# 2_0.net
KiCad netlist of a schematic drawn in Altium Designer
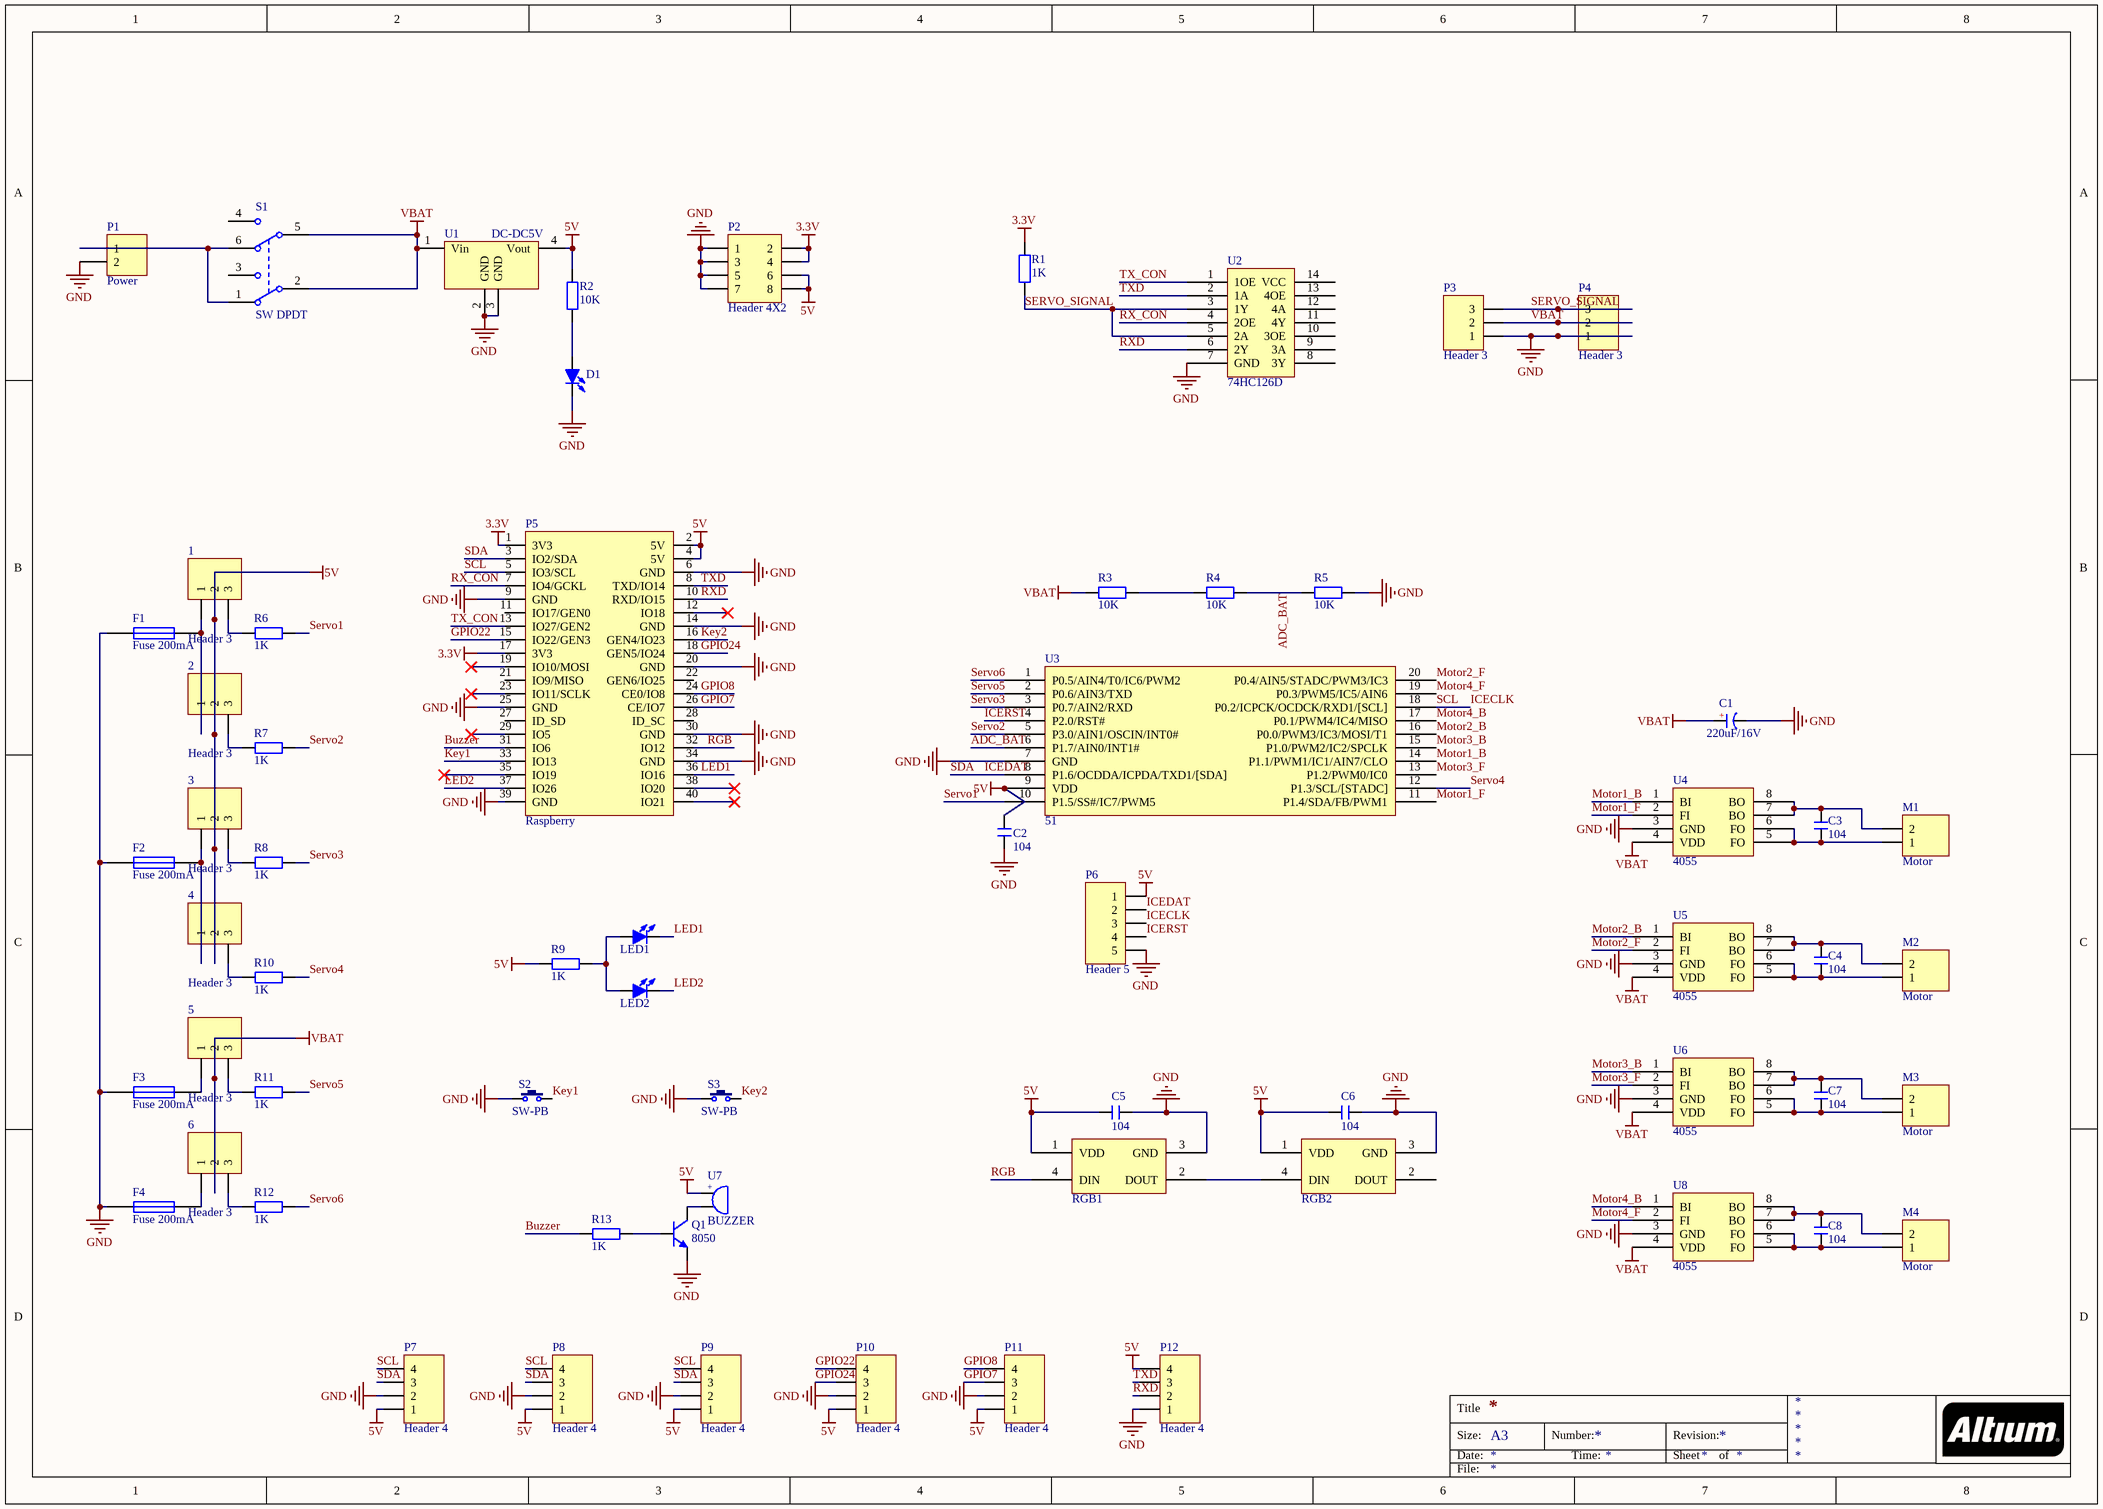
[diagram p0: 机械臂扩展板2.0.SchDoc]

(export (version "E")
  (design (tool "Eeschema 10.0.6"))
  (components
    (comp (ref "1")
      (value "Header 3")
      (footprint "HDR2.54-LI-3P")
      (description "舵机接口")
      (fields (field (name "版权归属") "源创客"))
      (libsource (lib "机械臂扩展板2.0") (part "Header 3"))
    )
    (comp (ref "2")
      (value "Header 3")
      (footprint "HDR2.54-LI-3P")
      (description "舵机接口")
      (fields (field (name "版权归属") "源创客"))
      (libsource (lib "机械臂扩展板2.0") (part "Header 3"))
    )
    (comp (ref "3")
      (value "Header 3")
      (footprint "HDR2.54-LI-3P")
      (description "舵机接口")
      (fields (field (name "版权归属") "源创客"))
      (libsource (lib "机械臂扩展板2.0") (part "Header 3"))
    )
    (comp (ref "4")
      (value "Header 3")
      (footprint "HDR2.54-LI-3P")
      (description "舵机接口")
      (fields (field (name "版权归属") "源创客"))
      (libsource (lib "机械臂扩展板2.0") (part "Header 3"))
    )
    (comp (ref "5")
      (value "Header 3")
      (footprint "HDR2.54-LI-3P")
      (description "舵机接口")
      (fields (field (name "版权归属") "源创客"))
      (libsource (lib "机械臂扩展板2.0") (part "Header 3"))
    )
    (comp (ref "6")
      (value "Header 3")
      (footprint "HDR2.54-LI-3P")
      (description "舵机接口")
      (fields (field (name "版权归属") "源创客"))
      (libsource (lib "机械臂扩展板2.0") (part "Header 3"))
    )
    (comp (ref "C1")
      (value "220uF/16V")
      (footprint "CM D(6.3*7.7)")
      (description "贴片电解电容")
      (fields (field (name "版权归属") "源创客"))
      (libsource (lib "机械臂扩展板2.0") (part "C-CM"))
    )
    (comp (ref "C2")
      (value "104")
      (footprint "C 0603_L")
      (description "无极性贴片电容")
      (fields (field (name "版权归属") "源创客"))
      (libsource (lib "机械臂扩展板2.0") (part "C"))
    )
    (comp (ref "C3")
      (value "104")
      (footprint "C 0603_L")
      (description "无极性贴片电容")
      (fields (field (name "版权归属") "源创客"))
      (libsource (lib "机械臂扩展板2.0") (part "C"))
    )
    (comp (ref "C4")
      (value "104")
      (footprint "C 0603_L")
      (description "无极性贴片电容")
      (fields (field (name "版权归属") "源创客"))
      (libsource (lib "机械臂扩展板2.0") (part "C"))
    )
    (comp (ref "C5")
      (value "104")
      (footprint "C 0603_L")
      (description "无极性贴片电容")
      (fields (field (name "版权归属") "源创客"))
      (libsource (lib "机械臂扩展板2.0") (part "C"))
    )
    (comp (ref "C6")
      (value "104")
      (footprint "C 0603_L")
      (description "无极性贴片电容")
      (fields (field (name "版权归属") "源创客"))
      (libsource (lib "机械臂扩展板2.0") (part "C"))
    )
    (comp (ref "C7")
      (value "104")
      (footprint "C 0603_L")
      (description "无极性贴片电容")
      (fields (field (name "版权归属") "源创客"))
      (libsource (lib "机械臂扩展板2.0") (part "C"))
    )
    (comp (ref "C8")
      (value "104")
      (footprint "C 0603_L")
      (description "无极性贴片电容")
      (fields (field (name "版权归属") "源创客"))
      (libsource (lib "机械臂扩展板2.0") (part "C"))
    )
    (comp (ref "D1")
      (value "红色")
      (footprint "LED 0603R")
      (description "贴片LED")
      (fields (field (name "版权归属") "源创客"))
      (libsource (lib "机械臂扩展板2.0") (part "LED-SMD"))
    )
    (comp (ref "F1")
      (value "Fuse 200mA")
      (footprint "F1206")
      (description "Fuse")
      (fields (field (name "PUBLISHER") "Altium Limited"))
      (libsource (lib "机械臂扩展板2.0") (part "Fuse 1"))
    )
    (comp (ref "F2")
      (value "Fuse 200mA")
      (footprint "F1206")
      (description "Fuse")
      (fields (field (name "PUBLISHER") "Altium Limited"))
      (libsource (lib "机械臂扩展板2.0") (part "Fuse 1"))
    )
    (comp (ref "F3")
      (value "Fuse 200mA")
      (footprint "F1206")
      (description "Fuse")
      (fields (field (name "PUBLISHER") "Altium Limited"))
      (libsource (lib "机械臂扩展板2.0") (part "Fuse 1"))
    )
    (comp (ref "F4")
      (value "Fuse 200mA")
      (footprint "F1206")
      (description "Fuse")
      (fields (field (name "PUBLISHER") "Altium Limited"))
      (libsource (lib "机械臂扩展板2.0") (part "Fuse 1"))
    )
    (comp (ref "LED1")
      (value "红色")
      (footprint "LED 0603G")
      (description "贴片LED")
      (fields (field (name "版权归属") "源创客"))
      (libsource (lib "机械臂扩展板2.0") (part "LED-SMD"))
    )
    (comp (ref "LED2")
      (value "红色")
      (footprint "LED 0603G")
      (description "贴片LED")
      (fields (field (name "版权归属") "源创客"))
      (libsource (lib "机械臂扩展板2.0") (part "LED-SMD"))
    )
    (comp (ref "M1")
      (value "Motor")
      (footprint "XH2.54-LI-2P")
      (description "2P接插件")
      (fields (field (name "版权归属") "源创客"))
      (libsource (lib "机械臂扩展板2.0") (part "Header 2"))
    )
    (comp (ref "M2")
      (value "Motor")
      (footprint "XH2.54-LI-2P")
      (description "2P接插件")
      (fields (field (name "版权归属") "源创客"))
      (libsource (lib "机械臂扩展板2.0") (part "Header 2"))
    )
    (comp (ref "M3")
      (value "Motor")
      (footprint "XH2.54-LI-2P")
      (description "2P接插件")
      (fields (field (name "版权归属") "源创客"))
      (libsource (lib "机械臂扩展板2.0") (part "Header 2"))
    )
    (comp (ref "M4")
      (value "Motor")
      (footprint "XH2.54-LI-2P")
      (description "2P接插件")
      (fields (field (name "版权归属") "源创客"))
      (libsource (lib "机械臂扩展板2.0") (part "Header 2"))
    )
    (comp (ref "P1") (value "Power") (footprint "KF128-3.81-2P") (libsource (lib "机械臂扩展板2.0") (part "Power")))
    (comp (ref "P2")
      (value "Header 4X2")
      (footprint "HDR2.54-LI-2x4P")
      (description "4*2P接插件")
      (fields (field (name "版权归属") "源创客"))
      (libsource (lib "机械臂扩展板2.0") (part "Header 4X2"))
    )
    (comp (ref "P3")
      (value "Header 3")
      (footprint "XH2.54-LI-3P")
      (description "舵机接口")
      (fields (field (name "版权归属") "源创客"))
      (libsource (lib "") (part "Header 3_2"))
    )
    (comp (ref "P4")
      (value "Header 3")
      (footprint "XH2.54-LI-3P")
      (description "舵机接口")
      (fields (field (name "版权归属") "源创客"))
      (libsource (lib "") (part "Header 3_1"))
    )
    (comp (ref "P6")
      (value "Header 5")
      (footprint "HDR2.54-LI-5P")
      (description "5P接插件")
      (fields (field (name "版权归属") "源创客"))
      (libsource (lib "机械臂扩展板2.0") (part "Header 5"))
    )
    (comp (ref "P7")
      (value "Header 4")
      (footprint "XH2.54-WI-4P")
      (description "I2C总线接口")
      (fields (field (name "版权归属") "源创客"))
      (libsource (lib "机械臂扩展板2.0") (part "Header 4"))
    )
    (comp (ref "P8")
      (value "Header 4")
      (footprint "XH2.54-WI-4P")
      (description "I2C总线接口")
      (fields (field (name "版权归属") "源创客"))
      (libsource (lib "机械臂扩展板2.0") (part "Header 4"))
    )
    (comp (ref "P9")
      (value "Header 4")
      (footprint "XH2.54-WI-4P")
      (description "I2C总线接口")
      (fields (field (name "版权归属") "源创客"))
      (libsource (lib "机械臂扩展板2.0") (part "Header 4"))
    )
    (comp (ref "P10")
      (value "Header 4")
      (footprint "XH2.54-LI-4P")
      (description "I2C总线接口")
      (fields (field (name "版权归属") "源创客"))
      (libsource (lib "机械臂扩展板2.0") (part "Header 4"))
    )
    (comp (ref "P11")
      (value "Header 4")
      (footprint "XH2.54-LI-4P")
      (description "I2C总线接口")
      (fields (field (name "版权归属") "源创客"))
      (libsource (lib "机械臂扩展板2.0") (part "Header 4"))
    )
    (comp (ref "P12")
      (value "Header 4")
      (footprint "HDR2.54-LI-4P")
      (description "I2C总线接口")
      (fields (field (name "版权归属") "源创客"))
      (libsource (lib "机械臂扩展板2.0") (part "Header 4"))
    )
    (comp (ref "Q1")
      (value "8050")
      (footprint "SOT23-3L")
      (description "高频放大-NPN型")
      (fields (field (name "版权归属") "源创客"))
      (libsource (lib "机械臂扩展板2.0") (part "8050-SMD"))
    )
    (comp (ref "R1")
      (value "1K")
      (footprint "R 0603_L")
      (description "贴片电阻")
      (fields (field (name "版权归属") "源创客"))
      (libsource (lib "机械臂扩展板2.0") (part "R"))
    )
    (comp (ref "R2")
      (value "10K")
      (footprint "R 0603_L")
      (description "贴片电阻")
      (fields (field (name "版权归属") "源创客"))
      (libsource (lib "机械臂扩展板2.0") (part "R"))
    )
    (comp (ref "R3")
      (value "10K")
      (footprint "R 0603_L")
      (description "贴片电阻")
      (fields (field (name "版权归属") "源创客"))
      (libsource (lib "机械臂扩展板2.0") (part "R"))
    )
    (comp (ref "R4")
      (value "10K")
      (footprint "R 0603_L")
      (description "贴片电阻")
      (fields (field (name "版权归属") "源创客"))
      (libsource (lib "机械臂扩展板2.0") (part "R"))
    )
    (comp (ref "R5")
      (value "10K")
      (footprint "R 0603_L")
      (description "贴片电阻")
      (fields (field (name "版权归属") "源创客"))
      (libsource (lib "机械臂扩展板2.0") (part "R"))
    )
    (comp (ref "R6")
      (value "1K")
      (footprint "R 0603_L")
      (description "贴片电阻")
      (fields (field (name "版权归属") "源创客"))
      (libsource (lib "机械臂扩展板2.0") (part "R"))
    )
    (comp (ref "R7")
      (value "1K")
      (footprint "R 0603_L")
      (description "贴片电阻")
      (fields (field (name "版权归属") "源创客"))
      (libsource (lib "机械臂扩展板2.0") (part "R"))
    )
    (comp (ref "R8")
      (value "1K")
      (footprint "R 0603_L")
      (description "贴片电阻")
      (fields (field (name "版权归属") "源创客"))
      (libsource (lib "机械臂扩展板2.0") (part "R"))
    )
    (comp (ref "R9")
      (value "1K")
      (footprint "R 0603_L")
      (description "贴片电阻")
      (fields (field (name "版权归属") "源创客"))
      (libsource (lib "机械臂扩展板2.0") (part "R"))
    )
    (comp (ref "R10")
      (value "1K")
      (footprint "R 0603_L")
      (description "贴片电阻")
      (fields (field (name "版权归属") "源创客"))
      (libsource (lib "机械臂扩展板2.0") (part "R"))
    )
    (comp (ref "R11")
      (value "1K")
      (footprint "R 0603_L")
      (description "贴片电阻")
      (fields (field (name "版权归属") "源创客"))
      (libsource (lib "机械臂扩展板2.0") (part "R"))
    )
    (comp (ref "R12")
      (value "1K")
      (footprint "R 0603_L")
      (description "贴片电阻")
      (fields (field (name "版权归属") "源创客"))
      (libsource (lib "机械臂扩展板2.0") (part "R"))
    )
    (comp (ref "R13")
      (value "1K")
      (footprint "R 0603_L")
      (description "贴片电阻")
      (fields (field (name "版权归属") "源创客"))
      (libsource (lib "机械臂扩展板2.0") (part "R"))
    )
    (comp (ref "Raspberry")
      (value "P5")
      (footprint "HDR2.54-LI-2x20P")
      (description "树莓派接口")
      (fields (field (name "版权归属") "源创客"))
      (libsource (lib "机械臂扩展板2.0") (part "Header 20X2"))
    )
    (comp (ref "RGB1") (value "~") (footprint "LED 3528-4Pin") (libsource (lib "机械臂扩展板2.0") (part "RGBLED")))
    (comp (ref "RGB2") (value "~") (footprint "LED 3528-4Pin") (libsource (lib "机械臂扩展板2.0") (part "RGBLED")))
    (comp (ref "S1")
      (value "SW DPDT")
      (footprint "SK-22D02")
      (description "2路波动开关")
      (fields (field (name "版权归属") "源创客"))
      (libsource (lib "机械臂扩展板2.0") (part "SSW-2P"))
    )
    (comp (ref "S2")
      (value "SW-PB")
      (footprint "TSW SMD-3*6*4.3")
      (description "3x6轻触开关")
      (fields (field (name "版权归属") "源创客"))
      (libsource (lib "机械臂扩展板2.0") (part "TSW 3x6"))
    )
    (comp (ref "S3")
      (value "SW-PB")
      (footprint "TSW SMD-3*6*4.3")
      (description "3x6轻触开关")
      (fields (field (name "版权归属") "源创客"))
      (libsource (lib "机械臂扩展板2.0") (part "TSW 3x6"))
    )
    (comp (ref "U1") (value "DC-DC5V") (footprint "升压模块") (libsource (lib "机械臂扩展板2.0") (part "DC-DC5V")))
    (comp (ref "U2") (value "74HC126D") (footprint "SOP14_L") (libsource (lib "机械臂扩展板2.0") (part "74HC126D")))
    (comp (ref "U3") (value "51") (footprint "TSSOP20_L") (libsource (lib "机械臂扩展板2.0") (part "51")))
    (comp (ref "U4") (value "4055") (footprint "SOP8_L") (libsource (lib "机械臂扩展板2.0") (part "4055")))
    (comp (ref "U5") (value "4055") (footprint "SOP8_L") (libsource (lib "机械臂扩展板2.0") (part "4055")))
    (comp (ref "U6") (value "4055") (footprint "SOP8_L") (libsource (lib "机械臂扩展板2.0") (part "4055")))
    (comp (ref "U7")
      (value "BUZZER")
      (footprint "BEEP 5x9x5.5")
      (description "蜂鸣器")
      (fields (field (name "版权归属") "源创客"))
      (libsource (lib "机械臂扩展板2.0") (part "BEEP"))
    )
    (comp (ref "U8") (value "4055") (footprint "SOP8_L") (libsource (lib "机械臂扩展板2.0") (part "4055")))
  )
  (nets
    (net (code "1") (name "/ADC_BAT") (class "Default")
      (node (ref "R4") (pin "2") (pinfunction "2_2") (pintype "passive"))
      (node (ref "R5") (pin "1") (pinfunction "1_1") (pintype "passive"))
      (node (ref "U3") (pin "6") (pinfunction "P1.7/AIN0/INT1#_6") (pintype "passive"))
    )
    (net (code "2") (name "/Buzzer") (class "Default")
      (node (ref "R13") (pin "1") (pinfunction "1_1") (pintype "passive"))
      (node (ref "Raspberry") (pin "31") (pinfunction "IO6_31") (pintype "passive"))
    )
    (net (code "3") (name "/GPIO7") (class "Default")
      (node (ref "P11") (pin "3") (pinfunction "3_3") (pintype "passive"))
      (node (ref "Raspberry") (pin "26") (pinfunction "CE/IO7_26") (pintype "passive"))
    )
    (net (code "4") (name "/GPIO8") (class "Default")
      (node (ref "P11") (pin "4") (pinfunction "4_4") (pintype "passive"))
      (node (ref "Raspberry") (pin "24") (pinfunction "CE0/IO8_24") (pintype "passive"))
    )
    (net (code "5") (name "/GPIO22") (class "Default")
      (node (ref "P10") (pin "4") (pinfunction "4_4") (pintype "passive"))
      (node (ref "Raspberry") (pin "15") (pinfunction "IO22/GEN3_15") (pintype "passive"))
    )
    (net (code "6") (name "/GPIO24") (class "Default")
      (node (ref "P10") (pin "3") (pinfunction "3_3") (pintype "passive"))
      (node (ref "Raspberry") (pin "18") (pinfunction "GEN5/IO24_18") (pintype "passive"))
    )
    (net (code "7") (name "/ICECLK") (class "Default")
      (node (ref "P6") (pin "3") (pinfunction "3_3") (pintype "passive"))
      (node (ref "P7") (pin "4") (pinfunction "4_4") (pintype "passive"))
      (node (ref "P8") (pin "4") (pinfunction "4_4") (pintype "passive"))
      (node (ref "P9") (pin "4") (pinfunction "4_4") (pintype "passive"))
      (node (ref "Raspberry") (pin "5") (pinfunction "IO3/SCL_5") (pintype "passive"))
      (node (ref "U3") (pin "18") (pinfunction "P0.2/ICPCK/OCDCK/RXD1/[SCL]_18") (pintype "passive"))
    )
    (net (code "8") (name "/ICEDAT") (class "Default")
      (node (ref "P6") (pin "2") (pinfunction "2_2") (pintype "passive"))
      (node (ref "P7") (pin "3") (pinfunction "3_3") (pintype "passive"))
      (node (ref "P8") (pin "3") (pinfunction "3_3") (pintype "passive"))
      (node (ref "P9") (pin "3") (pinfunction "3_3") (pintype "passive"))
      (node (ref "Raspberry") (pin "3") (pinfunction "IO2/SDA_3") (pintype "passive"))
      (node (ref "U3") (pin "8") (pinfunction "P1.6/OCDDA/ICPDA/TXD1/[SDA]_8") (pintype "passive"))
    )
    (net (code "9") (name "/ICERST") (class "Default")
      (node (ref "P6") (pin "4") (pinfunction "4_4") (pintype "passive"))
      (node (ref "U3") (pin "4") (pinfunction "P2.0/RST#_4") (pintype "passive"))
    )
    (net (code "10") (name "/Key1") (class "Default")
      (node (ref "Raspberry") (pin "33") (pinfunction "IO13_33") (pintype "passive"))
      (node (ref "S2") (pin "2") (pinfunction "2_2") (pintype "passive"))
    )
    (net (code "11") (name "/Key2") (class "Default")
      (node (ref "Raspberry") (pin "16") (pinfunction "GEN4/IO23_16") (pintype "passive"))
      (node (ref "S3") (pin "2") (pinfunction "2_2") (pintype "passive"))
    )
    (net (code "12") (name "/LED1") (class "Default")
      (node (ref "LED1") (pin "2") (pinfunction "K_2") (pintype "passive"))
      (node (ref "Raspberry") (pin "36") (pinfunction "IO16_36") (pintype "passive"))
    )
    (net (code "13") (name "/LED2") (class "Default")
      (node (ref "LED2") (pin "2") (pinfunction "K_2") (pintype "passive"))
      (node (ref "Raspberry") (pin "37") (pinfunction "IO26_37") (pintype "passive"))
    )
    (net (code "14") (name "/Motor1_B") (class "Default")
      (node (ref "U3") (pin "14") (pinfunction "P1.1/PWM1/IC1/AIN7/CLO_14") (pintype "passive"))
      (node (ref "U4") (pin "1") (pinfunction "BI_1") (pintype "passive"))
    )
    (net (code "15") (name "/Motor1_F") (class "Default")
      (node (ref "U3") (pin "11") (pinfunction "P1.4/SDA/FB/PWM1_11") (pintype "passive"))
      (node (ref "U4") (pin "2") (pinfunction "FI_2") (pintype "passive"))
    )
    (net (code "16") (name "/Motor2_B") (class "Default")
      (node (ref "U3") (pin "16") (pinfunction "P0.0/PWM3/IC3/MOSI/T1_16") (pintype "passive"))
      (node (ref "U5") (pin "1") (pinfunction "BI_1") (pintype "passive"))
    )
    (net (code "17") (name "/Motor2_F") (class "Default")
      (node (ref "U3") (pin "20") (pinfunction "P0.4/AIN5/STADC/PWM3/IC3_20") (pintype "passive"))
      (node (ref "U5") (pin "2") (pinfunction "FI_2") (pintype "passive"))
    )
    (net (code "18") (name "/Motor3_B") (class "Default")
      (node (ref "U3") (pin "15") (pinfunction "P1.0/PWM2/IC2/SPCLK_15") (pintype "passive"))
      (node (ref "U6") (pin "1") (pinfunction "BI_1") (pintype "passive"))
    )
    (net (code "19") (name "/Motor3_F") (class "Default")
      (node (ref "U3") (pin "13") (pinfunction "P1.2/PWM0/IC0_13") (pintype "passive"))
      (node (ref "U6") (pin "2") (pinfunction "FI_2") (pintype "passive"))
    )
    (net (code "20") (name "/Motor4_B") (class "Default")
      (node (ref "U3") (pin "17") (pinfunction "P0.1/PWM4/IC4/MISO_17") (pintype "passive"))
      (node (ref "U8") (pin "1") (pinfunction "BI_1") (pintype "passive"))
    )
    (net (code "21") (name "/Motor4_F") (class "Default")
      (node (ref "U3") (pin "19") (pinfunction "P0.3/PWM5/IC5/AIN6_19") (pintype "passive"))
      (node (ref "U8") (pin "2") (pinfunction "FI_2") (pintype "passive"))
    )
    (net (code "22") (name "/RGB") (class "Default")
      (node (ref "RGB1") (pin "4") (pinfunction "DIN_4") (pintype "passive"))
      (node (ref "Raspberry") (pin "32") (pinfunction "IO12_32") (pintype "passive"))
    )
    (net (code "23") (name "/RXD") (class "Default")
      (node (ref "P12") (pin "2") (pinfunction "2_2") (pintype "passive"))
      (node (ref "Raspberry") (pin "10") (pinfunction "RXD/IO15_10") (pintype "passive"))
      (node (ref "U2") (pin "6") (pinfunction "2Y_6") (pintype "passive"))
    )
    (net (code "24") (name "/RX_CON") (class "Default")
      (node (ref "Raspberry") (pin "7") (pinfunction "IO4/GCKL_7") (pintype "passive"))
      (node (ref "U2") (pin "4") (pinfunction "2OE_4") (pintype "passive"))
    )
    (net (code "25") (name "/SERVO_SIGNAL") (class "Default")
      (node (ref "P3") (pin "3") (pinfunction "3_3") (pintype "passive"))
      (node (ref "P4") (pin "3") (pinfunction "3_3") (pintype "passive"))
      (node (ref "R1") (pin "1") (pinfunction "1_1") (pintype "passive"))
      (node (ref "U2") (pin "3") (pinfunction "1Y_3") (pintype "passive"))
      (node (ref "U2") (pin "5") (pinfunction "2A_5") (pintype "passive"))
    )
    (net (code "26") (name "/Servo1") (class "Default")
      (node (ref "R6") (pin "2") (pinfunction "2_2") (pintype "passive"))
      (node (ref "U3") (pin "10") (pinfunction "P1.5/SS#/IC7/PWM5_10") (pintype "passive"))
    )
    (net (code "27") (name "/Servo2") (class "Default")
      (node (ref "R7") (pin "2") (pinfunction "2_2") (pintype "passive"))
      (node (ref "U3") (pin "5") (pinfunction "P3.0/AIN1/OSCIN/INT0#_5") (pintype "passive"))
    )
    (net (code "28") (name "/Servo3") (class "Default")
      (node (ref "R8") (pin "2") (pinfunction "2_2") (pintype "passive"))
      (node (ref "U3") (pin "3") (pinfunction "P0.7/AIN2/RXD_3") (pintype "passive"))
    )
    (net (code "29") (name "/Servo4") (class "Default")
      (node (ref "R10") (pin "2") (pinfunction "2_2") (pintype "passive"))
      (node (ref "U3") (pin "12") (pinfunction "P1.3/SCL/[STADC]_12") (pintype "passive"))
    )
    (net (code "30") (name "/Servo5") (class "Default")
      (node (ref "R11") (pin "2") (pinfunction "2_2") (pintype "passive"))
      (node (ref "U3") (pin "2") (pinfunction "P0.6/AIN3/TXD_2") (pintype "passive"))
    )
    (net (code "31") (name "/Servo6") (class "Default")
      (node (ref "R12") (pin "2") (pinfunction "2_2") (pintype "passive"))
      (node (ref "U3") (pin "1") (pinfunction "P0.5/AIN4/T0/IC6/PWM2_1") (pintype "passive"))
    )
    (net (code "32") (name "/TXD") (class "Default")
      (node (ref "P12") (pin "3") (pinfunction "3_3") (pintype "passive"))
      (node (ref "Raspberry") (pin "8") (pinfunction "TXD/IO14_8") (pintype "passive"))
      (node (ref "U2") (pin "2") (pinfunction "1A_2") (pintype "passive"))
    )
    (net (code "33") (name "/TX_CON") (class "Default")
      (node (ref "Raspberry") (pin "13") (pinfunction "IO27/GEN2_13") (pintype "passive"))
      (node (ref "U2") (pin "1") (pinfunction "1OE_1") (pintype "passive"))
    )
    (net (code "34") (name "3.3V") (class "Default")
      (node (ref "P2") (pin "2") (pinfunction "2_2") (pintype "passive"))
      (node (ref "P2") (pin "4") (pinfunction "4_4") (pintype "passive"))
      (node (ref "R1") (pin "2") (pinfunction "2_2") (pintype "passive"))
      (node (ref "Raspberry") (pin "1") (pinfunction "3V3_1") (pintype "passive"))
      (node (ref "Raspberry") (pin "17") (pinfunction "3V3_17") (pintype "passive"))
    )
    (net (code "35") (name "5V") (class "Default")
      (node (ref "1") (pin "2") (pinfunction "2_2") (pintype "passive"))
      (node (ref "2") (pin "2") (pinfunction "2_2") (pintype "passive"))
      (node (ref "3") (pin "2") (pinfunction "2_2") (pintype "passive"))
      (node (ref "4") (pin "2") (pinfunction "2_2") (pintype "passive"))
      (node (ref "C2") (pin "2") (pinfunction "2_2") (pintype "passive"))
      (node (ref "C5") (pin "1") (pinfunction "1_1") (pintype "passive"))
      (node (ref "C6") (pin "1") (pinfunction "1_1") (pintype "passive"))
      (node (ref "P10") (pin "1") (pinfunction "1_1") (pintype "passive"))
      (node (ref "P11") (pin "1") (pinfunction "1_1") (pintype "passive"))
      (node (ref "P12") (pin "4") (pinfunction "4_4") (pintype "passive"))
      (node (ref "P2") (pin "6") (pinfunction "6_6") (pintype "passive"))
      (node (ref "P2") (pin "8") (pinfunction "8_8") (pintype "passive"))
      (node (ref "P6") (pin "1") (pinfunction "1_1") (pintype "passive"))
      (node (ref "P7") (pin "1") (pinfunction "1_1") (pintype "passive"))
      (node (ref "P8") (pin "1") (pinfunction "1_1") (pintype "passive"))
      (node (ref "P9") (pin "1") (pinfunction "1_1") (pintype "passive"))
      (node (ref "R2") (pin "2") (pinfunction "2_2") (pintype "passive"))
      (node (ref "R9") (pin "1") (pinfunction "1_1") (pintype "passive"))
      (node (ref "RGB1") (pin "1") (pinfunction "VDD_1") (pintype "passive"))
      (node (ref "RGB2") (pin "1") (pinfunction "VDD_1") (pintype "passive"))
      (node (ref "Raspberry") (pin "2") (pinfunction "5V_2") (pintype "passive"))
      (node (ref "Raspberry") (pin "4") (pinfunction "5V_4") (pintype "passive"))
      (node (ref "U1") (pin "4") (pinfunction "Vout_4") (pintype "passive"))
      (node (ref "U3") (pin "9") (pinfunction "VDD_9") (pintype "passive"))
      (node (ref "U7") (pin "1") (pinfunction "1_1") (pintype "passive"))
    )
    (net (code "36") (name "GND") (class "Default")
      (node (ref "C1") (pin "2") (pinfunction "K_2") (pintype "passive"))
      (node (ref "C2") (pin "1") (pinfunction "1_1") (pintype "passive"))
      (node (ref "C5") (pin "2") (pinfunction "2_2") (pintype "passive"))
      (node (ref "C6") (pin "2") (pinfunction "2_2") (pintype "passive"))
      (node (ref "D1") (pin "2") (pinfunction "K_2") (pintype "passive"))
      (node (ref "F1") (pin "1") (pinfunction "1_1") (pintype "passive"))
      (node (ref "F2") (pin "1") (pinfunction "1_1") (pintype "passive"))
      (node (ref "F3") (pin "1") (pinfunction "1_1") (pintype "passive"))
      (node (ref "F4") (pin "1") (pinfunction "1_1") (pintype "passive"))
      (node (ref "P1") (pin "2") (pinfunction "2_2") (pintype "passive"))
      (node (ref "P10") (pin "2") (pinfunction "2_2") (pintype "passive"))
      (node (ref "P11") (pin "2") (pinfunction "2_2") (pintype "passive"))
      (node (ref "P12") (pin "1") (pinfunction "1_1") (pintype "passive"))
      (node (ref "P2") (pin "1") (pinfunction "1_1") (pintype "passive"))
      (node (ref "P2") (pin "3") (pinfunction "3_3") (pintype "passive"))
      (node (ref "P2") (pin "5") (pinfunction "5_5") (pintype "passive"))
      (node (ref "P2") (pin "7") (pinfunction "7_7") (pintype "passive"))
      (node (ref "P3") (pin "1") (pinfunction "1_1") (pintype "passive"))
      (node (ref "P4") (pin "1") (pinfunction "1_1") (pintype "passive"))
      (node (ref "P6") (pin "5") (pinfunction "5_5") (pintype "passive"))
      (node (ref "P7") (pin "2") (pinfunction "2_2") (pintype "passive"))
      (node (ref "P8") (pin "2") (pinfunction "2_2") (pintype "passive"))
      (node (ref "P9") (pin "2") (pinfunction "2_2") (pintype "passive"))
      (node (ref "Q1") (pin "2") (pinfunction "E_2") (pintype "passive"))
      (node (ref "R5") (pin "2") (pinfunction "2_2") (pintype "passive"))
      (node (ref "RGB1") (pin "3") (pinfunction "GND_3") (pintype "passive"))
      (node (ref "RGB2") (pin "3") (pinfunction "GND_3") (pintype "passive"))
      (node (ref "Raspberry") (pin "14") (pinfunction "GND_14") (pintype "passive"))
      (node (ref "Raspberry") (pin "20") (pinfunction "GND_20") (pintype "passive"))
      (node (ref "Raspberry") (pin "25") (pinfunction "GND_25") (pintype "passive"))
      (node (ref "Raspberry") (pin "30") (pinfunction "GND_30") (pintype "passive"))
      (node (ref "Raspberry") (pin "34") (pinfunction "GND_34") (pintype "passive"))
      (node (ref "Raspberry") (pin "39") (pinfunction "GND_39") (pintype "passive"))
      (node (ref "Raspberry") (pin "6") (pinfunction "GND_6") (pintype "passive"))
      (node (ref "Raspberry") (pin "9") (pinfunction "GND_9") (pintype "passive"))
      (node (ref "S2") (pin "1") (pinfunction "1_1") (pintype "passive"))
      (node (ref "S3") (pin "1") (pinfunction "1_1") (pintype "passive"))
      (node (ref "U1") (pin "2") (pinfunction "GND_2") (pintype "passive"))
      (node (ref "U1") (pin "3") (pinfunction "GND_3") (pintype "passive"))
      (node (ref "U2") (pin "7") (pinfunction "GND_7") (pintype "passive"))
      (node (ref "U3") (pin "7") (pinfunction "GND_7") (pintype "passive"))
      (node (ref "U4") (pin "3") (pinfunction "GND_3") (pintype "passive"))
      (node (ref "U5") (pin "3") (pinfunction "GND_3") (pintype "passive"))
      (node (ref "U6") (pin "3") (pinfunction "GND_3") (pintype "passive"))
      (node (ref "U8") (pin "3") (pinfunction "GND_3") (pintype "passive"))
    )
    (net (code "37") (name "Net-(1-Pad1)") (class "Default")
      (node (ref "1") (pin "1") (pinfunction "1_1") (pintype "passive"))
      (node (ref "2") (pin "1") (pinfunction "1_1") (pintype "passive"))
      (node (ref "F1") (pin "2") (pinfunction "2_2") (pintype "passive"))
    )
    (net (code "38") (name "Net-(1-Pad3)") (class "Default")
      (node (ref "1") (pin "3") (pinfunction "3_3") (pintype "passive"))
      (node (ref "R6") (pin "1") (pinfunction "1_1") (pintype "passive"))
    )
    (net (code "39") (name "Net-(2-Pad3)") (class "Default")
      (node (ref "2") (pin "3") (pinfunction "3_3") (pintype "passive"))
      (node (ref "R7") (pin "1") (pinfunction "1_1") (pintype "passive"))
    )
    (net (code "40") (name "Net-(3-Pad1)") (class "Default")
      (node (ref "3") (pin "1") (pinfunction "1_1") (pintype "passive"))
      (node (ref "4") (pin "1") (pinfunction "1_1") (pintype "passive"))
      (node (ref "F2") (pin "2") (pinfunction "2_2") (pintype "passive"))
    )
    (net (code "41") (name "Net-(3-Pad3)") (class "Default")
      (node (ref "3") (pin "3") (pinfunction "3_3") (pintype "passive"))
      (node (ref "R8") (pin "1") (pinfunction "1_1") (pintype "passive"))
    )
    (net (code "42") (name "Net-(4-Pad3)") (class "Default")
      (node (ref "4") (pin "3") (pinfunction "3_3") (pintype "passive"))
      (node (ref "R10") (pin "1") (pinfunction "1_1") (pintype "passive"))
    )
    (net (code "43") (name "Net-(5-Pad1)") (class "Default")
      (node (ref "5") (pin "1") (pinfunction "1_1") (pintype "passive"))
      (node (ref "F3") (pin "2") (pinfunction "2_2") (pintype "passive"))
    )
    (net (code "44") (name "Net-(5-Pad3)") (class "Default")
      (node (ref "5") (pin "3") (pinfunction "3_3") (pintype "passive"))
      (node (ref "R11") (pin "1") (pinfunction "1_1") (pintype "passive"))
    )
    (net (code "45") (name "Net-(6-Pad1)") (class "Default")
      (node (ref "6") (pin "1") (pinfunction "1_1") (pintype "passive"))
      (node (ref "F4") (pin "2") (pinfunction "2_2") (pintype "passive"))
    )
    (net (code "46") (name "Net-(6-Pad3)") (class "Default")
      (node (ref "6") (pin "3") (pinfunction "3_3") (pintype "passive"))
      (node (ref "R12") (pin "1") (pinfunction "1_1") (pintype "passive"))
    )
    (net (code "47") (name "Net-(C3-Pad1)") (class "Default")
      (node (ref "C3") (pin "1") (pinfunction "1_1") (pintype "passive"))
      (node (ref "M1") (pin "1") (pinfunction "1_1") (pintype "passive"))
      (node (ref "U4") (pin "5") (pinfunction "FO_5") (pintype "passive"))
      (node (ref "U4") (pin "6") (pinfunction "FO_6") (pintype "passive"))
    )
    (net (code "48") (name "Net-(C3-Pad2)") (class "Default")
      (node (ref "C3") (pin "2") (pinfunction "2_2") (pintype "passive"))
      (node (ref "M1") (pin "2") (pinfunction "2_2") (pintype "passive"))
      (node (ref "U4") (pin "7") (pinfunction "BO_7") (pintype "passive"))
      (node (ref "U4") (pin "8") (pinfunction "BO_8") (pintype "passive"))
    )
    (net (code "49") (name "Net-(C4-Pad1)") (class "Default")
      (node (ref "C4") (pin "1") (pinfunction "1_1") (pintype "passive"))
      (node (ref "M2") (pin "1") (pinfunction "1_1") (pintype "passive"))
      (node (ref "U5") (pin "5") (pinfunction "FO_5") (pintype "passive"))
      (node (ref "U5") (pin "6") (pinfunction "FO_6") (pintype "passive"))
    )
    (net (code "50") (name "Net-(C4-Pad2)") (class "Default")
      (node (ref "C4") (pin "2") (pinfunction "2_2") (pintype "passive"))
      (node (ref "M2") (pin "2") (pinfunction "2_2") (pintype "passive"))
      (node (ref "U5") (pin "7") (pinfunction "BO_7") (pintype "passive"))
      (node (ref "U5") (pin "8") (pinfunction "BO_8") (pintype "passive"))
    )
    (net (code "51") (name "Net-(C7-Pad1)") (class "Default")
      (node (ref "C7") (pin "1") (pinfunction "1_1") (pintype "passive"))
      (node (ref "M3") (pin "1") (pinfunction "1_1") (pintype "passive"))
      (node (ref "U6") (pin "5") (pinfunction "FO_5") (pintype "passive"))
      (node (ref "U6") (pin "6") (pinfunction "FO_6") (pintype "passive"))
    )
    (net (code "52") (name "Net-(C7-Pad2)") (class "Default")
      (node (ref "C7") (pin "2") (pinfunction "2_2") (pintype "passive"))
      (node (ref "M3") (pin "2") (pinfunction "2_2") (pintype "passive"))
      (node (ref "U6") (pin "7") (pinfunction "BO_7") (pintype "passive"))
      (node (ref "U6") (pin "8") (pinfunction "BO_8") (pintype "passive"))
    )
    (net (code "53") (name "Net-(C8-Pad1)") (class "Default")
      (node (ref "C8") (pin "1") (pinfunction "1_1") (pintype "passive"))
      (node (ref "M4") (pin "1") (pinfunction "1_1") (pintype "passive"))
      (node (ref "U8") (pin "5") (pinfunction "FO_5") (pintype "passive"))
      (node (ref "U8") (pin "6") (pinfunction "FO_6") (pintype "passive"))
    )
    (net (code "54") (name "Net-(C8-Pad2)") (class "Default")
      (node (ref "C8") (pin "2") (pinfunction "2_2") (pintype "passive"))
      (node (ref "M4") (pin "2") (pinfunction "2_2") (pintype "passive"))
      (node (ref "U8") (pin "7") (pinfunction "BO_7") (pintype "passive"))
      (node (ref "U8") (pin "8") (pinfunction "BO_8") (pintype "passive"))
    )
    (net (code "55") (name "Net-(D1-A)") (class "Default")
      (node (ref "D1") (pin "1") (pinfunction "A_1") (pintype "passive"))
      (node (ref "R2") (pin "1") (pinfunction "1_1") (pintype "passive"))
    )
    (net (code "56") (name "Net-(LED1-A)") (class "Default")
      (node (ref "LED1") (pin "1") (pinfunction "A_1") (pintype "passive"))
      (node (ref "LED2") (pin "1") (pinfunction "A_1") (pintype "passive"))
      (node (ref "R9") (pin "2") (pinfunction "2_2") (pintype "passive"))
    )
    (net (code "57") (name "Net-(P1-Pad1)") (class "Default")
      (node (ref "P1") (pin "1") (pinfunction "1_1") (pintype "passive"))
      (node (ref "S1") (pin "1") (pinfunction "1_1") (pintype "passive"))
      (node (ref "S1") (pin "6") (pinfunction "6_6") (pintype "passive"))
    )
    (net (code "58") (name "Net-(Q1-B)") (class "Default")
      (node (ref "Q1") (pin "1") (pinfunction "B_1") (pintype "passive"))
      (node (ref "R13") (pin "2") (pinfunction "2_2") (pintype "passive"))
    )
    (net (code "59") (name "Net-(Q1-C)") (class "Default")
      (node (ref "Q1") (pin "3") (pinfunction "C_3") (pintype "passive"))
      (node (ref "U7") (pin "2") (pinfunction "2_2") (pintype "passive"))
    )
    (net (code "60") (name "Net-(R3-Pad2)") (class "Default")
      (node (ref "R3") (pin "2") (pinfunction "2_2") (pintype "passive"))
      (node (ref "R4") (pin "1") (pinfunction "1_1") (pintype "passive"))
    )
    (net (code "61") (name "Net-(RGB1-DOUT)") (class "Default")
      (node (ref "RGB1") (pin "2") (pinfunction "DOUT_2") (pintype "passive"))
      (node (ref "RGB2") (pin "4") (pinfunction "DIN_4") (pintype "passive"))
    )
    (net (code "62") (name "VBAT") (class "Default")
      (node (ref "5") (pin "2") (pinfunction "2_2") (pintype "passive"))
      (node (ref "6") (pin "2") (pinfunction "2_2") (pintype "passive"))
      (node (ref "C1") (pin "1") (pinfunction "A_1") (pintype "passive"))
      (node (ref "P3") (pin "2") (pinfunction "2_2") (pintype "passive"))
      (node (ref "P4") (pin "2") (pinfunction "2_2") (pintype "passive"))
      (node (ref "R3") (pin "1") (pinfunction "1_1") (pintype "passive"))
      (node (ref "S1") (pin "2") (pinfunction "2_2") (pintype "passive"))
      (node (ref "S1") (pin "5") (pinfunction "5_5") (pintype "passive"))
      (node (ref "U1") (pin "1") (pinfunction "Vin_1") (pintype "passive"))
      (node (ref "U4") (pin "4") (pinfunction "VDD_4") (pintype "passive"))
      (node (ref "U5") (pin "4") (pinfunction "VDD_4") (pintype "passive"))
      (node (ref "U6") (pin "4") (pinfunction "VDD_4") (pintype "passive"))
      (node (ref "U8") (pin "4") (pinfunction "VDD_4") (pintype "passive"))
    )
    (net (code "63") (name "unconnected-(RGB2-DOUT-Pad2)") (class "Default")
      (node (ref "RGB2") (pin "2") (pinfunction "DOUT_2") (pintype "passive"))
    )
    (net (code "64") (name "unconnected-(Raspberry-GEN6{slash}IO25-Pad22)") (class "Default")
      (node (ref "Raspberry") (pin "22") (pinfunction "GEN6/IO25_22") (pintype "passive"))
    )
    (net (code "65") (name "unconnected-(Raspberry-ID_SC-Pad28)") (class "Default")
      (node (ref "Raspberry") (pin "28") (pinfunction "ID_SC_28") (pintype "passive"))
    )
    (net (code "66") (name "unconnected-(Raspberry-ID_SD-Pad27)") (class "Default")
      (node (ref "Raspberry") (pin "27") (pinfunction "ID_SD_27") (pintype "passive"))
    )
    (net (code "67") (name "unconnected-(Raspberry-IO5-Pad29)") (class "Default")
      (node (ref "Raspberry") (pin "29") (pinfunction "IO5_29") (pintype "passive+no_connect"))
    )
    (net (code "68") (name "unconnected-(Raspberry-IO9{slash}MISO-Pad21)") (class "Default")
      (node (ref "Raspberry") (pin "21") (pinfunction "IO9/MISO_21") (pintype "passive"))
    )
    (net (code "69") (name "unconnected-(Raspberry-IO10{slash}MOSI-Pad19)") (class "Default")
      (node (ref "Raspberry") (pin "19") (pinfunction "IO10/MOSI_19") (pintype "passive+no_connect"))
    )
    (net (code "70") (name "unconnected-(Raspberry-IO11{slash}SCLK-Pad23)") (class "Default")
      (node (ref "Raspberry") (pin "23") (pinfunction "IO11/SCLK_23") (pintype "passive+no_connect"))
    )
    (net (code "71") (name "unconnected-(Raspberry-IO17{slash}GEN0-Pad11)") (class "Default")
      (node (ref "Raspberry") (pin "11") (pinfunction "IO17/GEN0_11") (pintype "passive"))
    )
    (net (code "72") (name "unconnected-(Raspberry-IO18-Pad12)") (class "Default")
      (node (ref "Raspberry") (pin "12") (pinfunction "IO18_12") (pintype "passive+no_connect"))
    )
    (net (code "73") (name "unconnected-(Raspberry-IO19-Pad35)") (class "Default")
      (node (ref "Raspberry") (pin "35") (pinfunction "IO19_35") (pintype "passive+no_connect"))
    )
    (net (code "74") (name "unconnected-(Raspberry-IO20-Pad38)") (class "Default")
      (node (ref "Raspberry") (pin "38") (pinfunction "IO20_38") (pintype "passive+no_connect"))
    )
    (net (code "75") (name "unconnected-(Raspberry-IO21-Pad40)") (class "Default")
      (node (ref "Raspberry") (pin "40") (pinfunction "IO21_40") (pintype "passive+no_connect"))
    )
    (net (code "76") (name "unconnected-(S1-Pad3)") (class "Default")
      (node (ref "S1") (pin "3") (pinfunction "3_3") (pintype "passive"))
    )
    (net (code "77") (name "unconnected-(S1-Pad4)") (class "Default")
      (node (ref "S1") (pin "4") (pinfunction "4_4") (pintype "passive"))
    )
    (net (code "78") (name "unconnected-(U2-3A-Pad9)") (class "Default")
      (node (ref "U2") (pin "9") (pinfunction "3A_9") (pintype "passive"))
    )
    (net (code "79") (name "unconnected-(U2-3OE-Pad10)") (class "Default")
      (node (ref "U2") (pin "10") (pinfunction "3OE_10") (pintype "passive"))
    )
    (net (code "80") (name "unconnected-(U2-3Y-Pad8)") (class "Default")
      (node (ref "U2") (pin "8") (pinfunction "3Y_8") (pintype "passive"))
    )
    (net (code "81") (name "unconnected-(U2-4A-Pad12)") (class "Default")
      (node (ref "U2") (pin "12") (pinfunction "4A_12") (pintype "passive"))
    )
    (net (code "82") (name "unconnected-(U2-4OE-Pad13)") (class "Default")
      (node (ref "U2") (pin "13") (pinfunction "4OE_13") (pintype "passive"))
    )
    (net (code "83") (name "unconnected-(U2-4Y-Pad11)") (class "Default")
      (node (ref "U2") (pin "11") (pinfunction "4Y_11") (pintype "passive"))
    )
    (net (code "84") (name "unconnected-(U2-VCC-Pad14)") (class "Default")
      (node (ref "U2") (pin "14") (pinfunction "VCC_14") (pintype "passive"))
    )
  )
)
